# d232_board.net
KiCad netlist of a schematic drawn in EAGLE
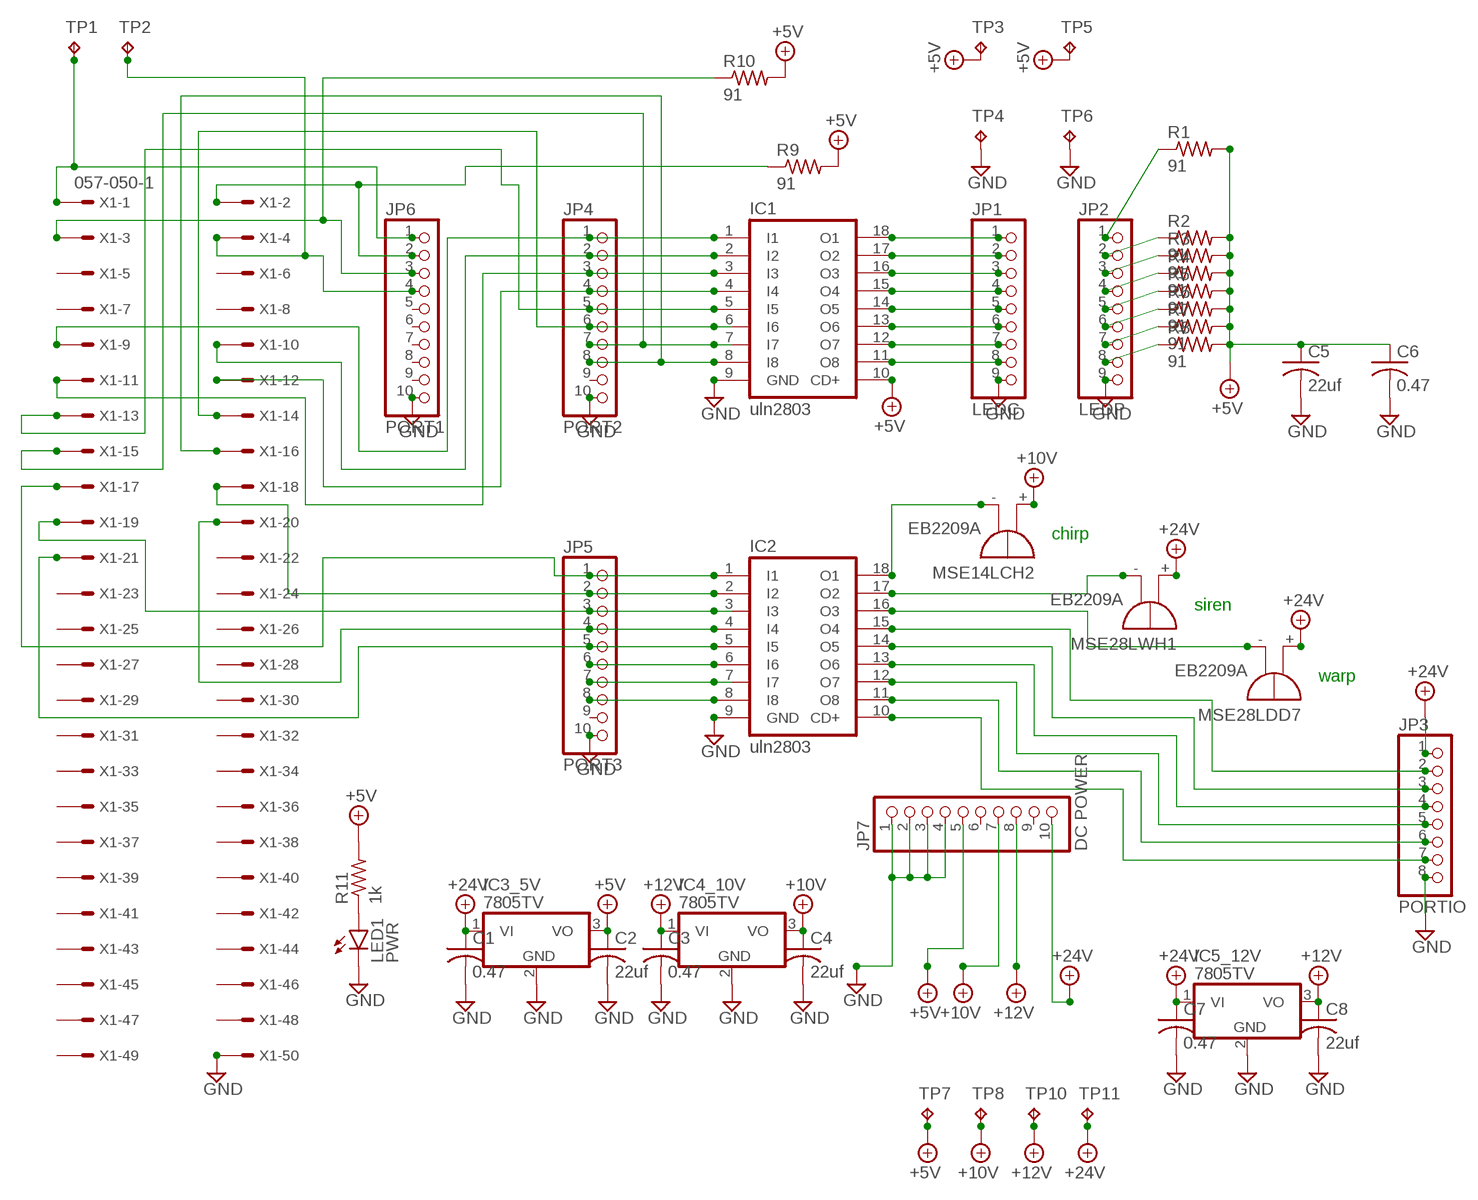
[diagram p0: schematic, sheet 1]

(export (version "E")
  (design (tool "Eeschema 10.0.6"))
  (components
    (comp (ref "C1")
      (value "0.47")
      (footprint "eagle-import:C1206K")
      (libsource (lib "eagle-import") (part "C-USC1206K"))
    )
    (comp (ref "C2")
      (value "22uf")
      (footprint "eagle-import:C1206K")
      (libsource (lib "eagle-import") (part "C-USC1206K"))
    )
    (comp (ref "C3")
      (value "0.47")
      (footprint "eagle-import:C1206K")
      (libsource (lib "eagle-import") (part "C-USC1206K"))
    )
    (comp (ref "C4")
      (value "22uf")
      (footprint "eagle-import:C1206K")
      (libsource (lib "eagle-import") (part "C-USC1206K"))
    )
    (comp (ref "C5")
      (value "22uf")
      (footprint "eagle-import:C1206K")
      (libsource (lib "eagle-import") (part "C-USC1206K"))
    )
    (comp (ref "C6")
      (value "0.47")
      (footprint "eagle-import:C1206K")
      (libsource (lib "eagle-import") (part "C-USC1206K"))
    )
    (comp (ref "C7")
      (value "0.47")
      (footprint "eagle-import:C1206K")
      (libsource (lib "eagle-import") (part "C-USC1206K"))
    )
    (comp (ref "C8")
      (value "22uf")
      (footprint "eagle-import:C1206K")
      (libsource (lib "eagle-import") (part "C-USC1206K"))
    )
    (comp (ref "IC1")
      (value "uln2803")
      (footprint "eagle-import:DIL18")
      (libsource (lib "eagle-import") (part "ULN2803A"))
    )
    (comp (ref "IC2")
      (value "uln2803")
      (footprint "eagle-import:DIL18")
      (libsource (lib "eagle-import") (part "ULN2803A"))
    )
    (comp (ref "IC3_5V")
      (value "7805TV")
      (footprint "eagle-import:TO220V")
      (libsource (lib "eagle-import") (part "78TV05"))
    )
    (comp (ref "IC4_10V")
      (value "7805TV")
      (footprint "eagle-import:TO220V")
      (libsource (lib "eagle-import") (part "78TV05"))
    )
    (comp (ref "IC5_12V")
      (value "7805TV")
      (footprint "eagle-import:TO220V")
      (libsource (lib "eagle-import") (part "78TV05"))
    )
    (comp (ref "JP1")
      (value "LEDC")
      (footprint "eagle-import:1X09")
      (libsource (lib "eagle-import") (part "PINHD-1X9"))
    )
    (comp (ref "JP2")
      (value "LEDP")
      (footprint "eagle-import:1X09")
      (libsource (lib "eagle-import") (part "PINHD-1X9"))
    )
    (comp (ref "JP3")
      (value "PORTIO")
      (footprint "eagle-import:1X08")
      (libsource (lib "eagle-import") (part "PINHD-1X8"))
    )
    (comp (ref "JP4")
      (value "PORT2")
      (footprint "eagle-import:1X10")
      (libsource (lib "eagle-import") (part "PINHD-1X10"))
    )
    (comp (ref "JP5")
      (value "PORT3")
      (footprint "eagle-import:1X10")
      (libsource (lib "eagle-import") (part "PINHD-1X10"))
    )
    (comp (ref "JP6")
      (value "PORT1")
      (footprint "eagle-import:1X10")
      (libsource (lib "eagle-import") (part "PINHD-1X10"))
    )
    (comp (ref "JP7")
      (value "DC POWER")
      (footprint "eagle-import:1X10")
      (libsource (lib "eagle-import") (part "PINHD-1X10"))
    )
    (comp (ref "LED1")
      (value "PWR")
      (footprint "eagle-import:CHIPLED_1206")
      (libsource (lib "eagle-import") (part "LEDCHIPLED_1206"))
    )
    (comp (ref "MSE14LCH2")
      (value "EB2209A")
      (footprint "eagle-import:EB2209A")
      (libsource (lib "eagle-import") (part "EB2209A"))
    )
    (comp (ref "MSE28LDD7")
      (value "EB2209A")
      (footprint "eagle-import:EB2209A")
      (libsource (lib "eagle-import") (part "EB2209A"))
    )
    (comp (ref "MSE28LWH1")
      (value "EB2209A")
      (footprint "eagle-import:EB2209A")
      (libsource (lib "eagle-import") (part "EB2209A"))
    )
    (comp (ref "R1")
      (value "91")
      (footprint "eagle-import:0204V")
      (libsource (lib "eagle-import") (part "R-US_0204/2V"))
    )
    (comp (ref "R2")
      (value "91")
      (footprint "eagle-import:0204V")
      (libsource (lib "eagle-import") (part "R-US_0204/2V"))
    )
    (comp (ref "R3")
      (value "91")
      (footprint "eagle-import:0204V")
      (libsource (lib "eagle-import") (part "R-US_0204/2V"))
    )
    (comp (ref "R4")
      (value "91")
      (footprint "eagle-import:0204V")
      (libsource (lib "eagle-import") (part "R-US_0204/2V"))
    )
    (comp (ref "R5")
      (value "91")
      (footprint "eagle-import:0204V")
      (libsource (lib "eagle-import") (part "R-US_0204/2V"))
    )
    (comp (ref "R6")
      (value "91")
      (footprint "eagle-import:0204V")
      (libsource (lib "eagle-import") (part "R-US_0204/2V"))
    )
    (comp (ref "R7")
      (value "91")
      (footprint "eagle-import:0204V")
      (libsource (lib "eagle-import") (part "R-US_0204/2V"))
    )
    (comp (ref "R8")
      (value "91")
      (footprint "eagle-import:0204V")
      (libsource (lib "eagle-import") (part "R-US_0204/2V"))
    )
    (comp (ref "R9")
      (value "91")
      (footprint "eagle-import:0204V")
      (libsource (lib "eagle-import") (part "R-US_0204/2V"))
    )
    (comp (ref "R10")
      (value "91")
      (footprint "eagle-import:0204V")
      (libsource (lib "eagle-import") (part "R-US_0204/2V"))
    )
    (comp (ref "R11")
      (value "1k")
      (footprint "eagle-import:0204V")
      (libsource (lib "eagle-import") (part "R-US_0204/2V"))
    )
    (comp (ref "TP1")
      (value "TPB2,54")
      (footprint "eagle-import:B2,54")
      (libsource (lib "eagle-import") (part "TPB2,54"))
    )
    (comp (ref "TP2")
      (value "TPB2,54")
      (footprint "eagle-import:B2,54")
      (libsource (lib "eagle-import") (part "TPB2,54"))
    )
    (comp (ref "TP3")
      (value "TPB2,54")
      (footprint "eagle-import:B2,54")
      (libsource (lib "eagle-import") (part "TPB2,54"))
    )
    (comp (ref "TP4")
      (value "TPB2,54")
      (footprint "eagle-import:B2,54")
      (libsource (lib "eagle-import") (part "TPB2,54"))
    )
    (comp (ref "TP5")
      (value "TPB2,54")
      (footprint "eagle-import:B2,54")
      (libsource (lib "eagle-import") (part "TPB2,54"))
    )
    (comp (ref "TP6")
      (value "TPB2,54")
      (footprint "eagle-import:B2,54")
      (libsource (lib "eagle-import") (part "TPB2,54"))
    )
    (comp (ref "TP7")
      (value "TPB2,54")
      (footprint "eagle-import:B2,54")
      (libsource (lib "eagle-import") (part "TPB2,54"))
    )
    (comp (ref "TP8")
      (value "TPB2,54")
      (footprint "eagle-import:B2,54")
      (libsource (lib "eagle-import") (part "TPB2,54"))
    )
    (comp (ref "TP10")
      (value "TPB2,54")
      (footprint "eagle-import:B2,54")
      (libsource (lib "eagle-import") (part "TPB2,54"))
    )
    (comp (ref "TP11")
      (value "TPB2,54")
      (footprint "eagle-import:B2,54")
      (libsource (lib "eagle-import") (part "TPB2,54"))
    )
    (comp (ref "X1")
      (value "057-050-1")
      (footprint "eagle-import:057-050-1")
      (libsource (lib "eagle-import") (part "057-050-1"))
    )
  )
  (nets
    (net (code "1") (name "+5V") (class "Default")
      (node (ref "C2") (pin "1") (pinfunction "1_1") (pintype "passive"))
      (node (ref "C5") (pin "1") (pinfunction "1_1") (pintype "passive"))
      (node (ref "C6") (pin "1") (pinfunction "1_1") (pintype "passive"))
      (node (ref "IC1") (pin "10") (pinfunction "CD+_10") (pintype "passive"))
      (node (ref "IC3_5V") (pin "3") (pinfunction "VO_3") (pintype "passive"))
      (node (ref "JP7") (pin "5") (pinfunction "5_5") (pintype "passive"))
      (node (ref "R1") (pin "2") (pinfunction "2_2") (pintype "passive"))
      (node (ref "R10") (pin "2") (pinfunction "2_2") (pintype "passive"))
      (node (ref "R11") (pin "2") (pinfunction "2_2") (pintype "passive"))
      (node (ref "R2") (pin "2") (pinfunction "2_2") (pintype "passive"))
      (node (ref "R3") (pin "2") (pinfunction "2_2") (pintype "passive"))
      (node (ref "R4") (pin "2") (pinfunction "2_2") (pintype "passive"))
      (node (ref "R5") (pin "2") (pinfunction "2_2") (pintype "passive"))
      (node (ref "R6") (pin "2") (pinfunction "2_2") (pintype "passive"))
      (node (ref "R7") (pin "2") (pinfunction "2_2") (pintype "passive"))
      (node (ref "R8") (pin "2") (pinfunction "2_2") (pintype "passive"))
      (node (ref "R9") (pin "2") (pinfunction "2_2") (pintype "passive"))
      (node (ref "TP3") (pin "TP") (pinfunction "TP_TP") (pintype "input"))
      (node (ref "TP5") (pin "TP") (pinfunction "TP_TP") (pintype "input"))
      (node (ref "TP7") (pin "TP") (pinfunction "TP_TP") (pintype "input"))
    )
    (net (code "2") (name "+10V") (class "Default")
      (node (ref "C4") (pin "1") (pinfunction "1_1") (pintype "passive"))
      (node (ref "IC4_10V") (pin "3") (pinfunction "VO_3") (pintype "passive"))
      (node (ref "JP7") (pin "7") (pinfunction "7_7") (pintype "passive"))
      (node (ref "MSE14LCH2") (pin "+") (pinfunction "+_+") (pintype "passive"))
      (node (ref "TP8") (pin "TP") (pinfunction "TP_TP") (pintype "input"))
    )
    (net (code "3") (name "+12V") (class "Default")
      (node (ref "C3") (pin "1") (pinfunction "1_1") (pintype "passive"))
      (node (ref "C8") (pin "1") (pinfunction "1_1") (pintype "passive"))
      (node (ref "IC4_10V") (pin "1") (pinfunction "VI_1") (pintype "input"))
      (node (ref "IC5_12V") (pin "3") (pinfunction "VO_3") (pintype "passive"))
      (node (ref "JP7") (pin "8") (pinfunction "8_8") (pintype "passive"))
      (node (ref "TP10") (pin "TP") (pinfunction "TP_TP") (pintype "input"))
    )
    (net (code "4") (name "+24V") (class "Default")
      (node (ref "C1") (pin "1") (pinfunction "1_1") (pintype "passive"))
      (node (ref "C7") (pin "1") (pinfunction "1_1") (pintype "passive"))
      (node (ref "IC3_5V") (pin "1") (pinfunction "VI_1") (pintype "input"))
      (node (ref "IC5_12V") (pin "1") (pinfunction "VI_1") (pintype "input"))
      (node (ref "JP3") (pin "1") (pinfunction "1_1") (pintype "passive"))
      (node (ref "JP7") (pin "10") (pinfunction "10_10") (pintype "passive"))
      (node (ref "MSE28LDD7") (pin "+") (pinfunction "+_+") (pintype "passive"))
      (node (ref "MSE28LWH1") (pin "+") (pinfunction "+_+") (pintype "passive"))
      (node (ref "TP11") (pin "TP") (pinfunction "TP_TP") (pintype "input"))
    )
    (net (code "5") (name "GND") (class "Default")
      (node (ref "C1") (pin "2") (pinfunction "2_2") (pintype "passive"))
      (node (ref "C2") (pin "2") (pinfunction "2_2") (pintype "passive"))
      (node (ref "C3") (pin "2") (pinfunction "2_2") (pintype "passive"))
      (node (ref "C4") (pin "2") (pinfunction "2_2") (pintype "passive"))
      (node (ref "C5") (pin "2") (pinfunction "2_2") (pintype "passive"))
      (node (ref "C6") (pin "2") (pinfunction "2_2") (pintype "passive"))
      (node (ref "C7") (pin "2") (pinfunction "2_2") (pintype "passive"))
      (node (ref "C8") (pin "2") (pinfunction "2_2") (pintype "passive"))
      (node (ref "IC1") (pin "9") (pinfunction "GND_9") (pintype "power_in"))
      (node (ref "IC2") (pin "9") (pinfunction "GND_9") (pintype "power_in"))
      (node (ref "IC3_5V") (pin "2") (pinfunction "GND_2") (pintype "passive"))
      (node (ref "IC4_10V") (pin "2") (pinfunction "GND_2") (pintype "passive"))
      (node (ref "IC5_12V") (pin "2") (pinfunction "GND_2") (pintype "passive"))
      (node (ref "JP1") (pin "9") (pinfunction "9_9") (pintype "passive"))
      (node (ref "JP2") (pin "9") (pinfunction "9_9") (pintype "passive"))
      (node (ref "JP3") (pin "8") (pinfunction "8_8") (pintype "passive"))
      (node (ref "JP4") (pin "10") (pinfunction "10_10") (pintype "passive"))
      (node (ref "JP5") (pin "10") (pinfunction "10_10") (pintype "passive"))
      (node (ref "JP6") (pin "10") (pinfunction "10_10") (pintype "passive"))
      (node (ref "JP7") (pin "1") (pinfunction "1_1") (pintype "passive"))
      (node (ref "JP7") (pin "2") (pinfunction "2_2") (pintype "passive"))
      (node (ref "JP7") (pin "3") (pinfunction "3_3") (pintype "passive"))
      (node (ref "JP7") (pin "4") (pinfunction "4_4") (pintype "passive"))
      (node (ref "LED1") (pin "C") (pinfunction "C_C") (pintype "passive"))
      (node (ref "TP4") (pin "TP") (pinfunction "TP_TP") (pintype "input"))
      (node (ref "TP6") (pin "TP") (pinfunction "TP_TP") (pintype "input"))
      (node (ref "X1") (pin "50") (pinfunction "S_50") (pintype "passive"))
    )
    (net (code "6") (name "Net-(IC1-I1)") (class "Default")
      (node (ref "IC1") (pin "1") (pinfunction "I1_1") (pintype "input"))
      (node (ref "JP4") (pin "1") (pinfunction "1_1") (pintype "passive"))
      (node (ref "X1") (pin "9") (pinfunction "S_9") (pintype "passive"))
    )
    (net (code "7") (name "Net-(IC1-I2)") (class "Default")
      (node (ref "IC1") (pin "2") (pinfunction "I2_2") (pintype "input"))
      (node (ref "JP4") (pin "2") (pinfunction "2_2") (pintype "passive"))
      (node (ref "X1") (pin "10") (pinfunction "S_10") (pintype "passive"))
    )
    (net (code "8") (name "Net-(IC1-I3)") (class "Default")
      (node (ref "IC1") (pin "3") (pinfunction "I3_3") (pintype "input"))
      (node (ref "JP4") (pin "3") (pinfunction "3_3") (pintype "passive"))
      (node (ref "X1") (pin "11") (pinfunction "S_11") (pintype "passive"))
    )
    (net (code "9") (name "Net-(IC1-I4)") (class "Default")
      (node (ref "IC1") (pin "4") (pinfunction "I4_4") (pintype "input"))
      (node (ref "JP4") (pin "4") (pinfunction "4_4") (pintype "passive"))
      (node (ref "X1") (pin "12") (pinfunction "S_12") (pintype "passive"))
    )
    (net (code "10") (name "Net-(IC1-I5)") (class "Default")
      (node (ref "IC1") (pin "5") (pinfunction "I5_5") (pintype "input"))
      (node (ref "JP4") (pin "5") (pinfunction "5_5") (pintype "passive"))
      (node (ref "X1") (pin "13") (pinfunction "S_13") (pintype "passive"))
    )
    (net (code "11") (name "Net-(IC1-I6)") (class "Default")
      (node (ref "IC1") (pin "6") (pinfunction "I6_6") (pintype "input"))
      (node (ref "JP4") (pin "6") (pinfunction "6_6") (pintype "passive"))
      (node (ref "X1") (pin "14") (pinfunction "S_14") (pintype "passive"))
    )
    (net (code "12") (name "Net-(IC1-I7)") (class "Default")
      (node (ref "IC1") (pin "7") (pinfunction "I7_7") (pintype "input"))
      (node (ref "JP4") (pin "7") (pinfunction "7_7") (pintype "passive"))
      (node (ref "X1") (pin "15") (pinfunction "S_15") (pintype "passive"))
    )
    (net (code "13") (name "Net-(IC1-I8)") (class "Default")
      (node (ref "IC1") (pin "8") (pinfunction "I8_8") (pintype "input"))
      (node (ref "JP4") (pin "8") (pinfunction "8_8") (pintype "passive"))
      (node (ref "X1") (pin "16") (pinfunction "S_16") (pintype "passive"))
    )
    (net (code "14") (name "Net-(IC1-O1)") (class "Default")
      (node (ref "IC1") (pin "18") (pinfunction "O1_18") (pintype "open_collector"))
      (node (ref "JP1") (pin "1") (pinfunction "1_1") (pintype "passive"))
    )
    (net (code "15") (name "Net-(IC1-O2)") (class "Default")
      (node (ref "IC1") (pin "17") (pinfunction "O2_17") (pintype "open_collector"))
      (node (ref "JP1") (pin "2") (pinfunction "2_2") (pintype "passive"))
    )
    (net (code "16") (name "Net-(IC1-O3)") (class "Default")
      (node (ref "IC1") (pin "16") (pinfunction "O3_16") (pintype "open_collector"))
      (node (ref "JP1") (pin "3") (pinfunction "3_3") (pintype "passive"))
    )
    (net (code "17") (name "Net-(IC1-O4)") (class "Default")
      (node (ref "IC1") (pin "15") (pinfunction "O4_15") (pintype "open_collector"))
      (node (ref "JP1") (pin "4") (pinfunction "4_4") (pintype "passive"))
    )
    (net (code "18") (name "Net-(IC1-O5)") (class "Default")
      (node (ref "IC1") (pin "14") (pinfunction "O5_14") (pintype "open_collector"))
      (node (ref "JP1") (pin "5") (pinfunction "5_5") (pintype "passive"))
    )
    (net (code "19") (name "Net-(IC1-O6)") (class "Default")
      (node (ref "IC1") (pin "13") (pinfunction "O6_13") (pintype "open_collector"))
      (node (ref "JP1") (pin "6") (pinfunction "6_6") (pintype "passive"))
    )
    (net (code "20") (name "Net-(IC1-O7)") (class "Default")
      (node (ref "IC1") (pin "12") (pinfunction "O7_12") (pintype "open_collector"))
      (node (ref "JP1") (pin "7") (pinfunction "7_7") (pintype "passive"))
    )
    (net (code "21") (name "Net-(IC1-O8)") (class "Default")
      (node (ref "IC1") (pin "11") (pinfunction "O8_11") (pintype "open_collector"))
      (node (ref "JP1") (pin "8") (pinfunction "8_8") (pintype "passive"))
    )
    (net (code "22") (name "Net-(IC2-CD+)") (class "Default")
      (node (ref "IC2") (pin "10") (pinfunction "CD+_10") (pintype "passive"))
      (node (ref "JP3") (pin "7") (pinfunction "7_7") (pintype "passive"))
    )
    (net (code "23") (name "Net-(IC2-I1)") (class "Default")
      (node (ref "IC2") (pin "1") (pinfunction "I1_1") (pintype "input"))
      (node (ref "JP5") (pin "1") (pinfunction "1_1") (pintype "passive"))
      (node (ref "X1") (pin "17") (pinfunction "S_17") (pintype "passive"))
    )
    (net (code "24") (name "Net-(IC2-I2)") (class "Default")
      (node (ref "IC2") (pin "2") (pinfunction "I2_2") (pintype "input"))
      (node (ref "JP5") (pin "2") (pinfunction "2_2") (pintype "passive"))
      (node (ref "X1") (pin "18") (pinfunction "S_18") (pintype "passive"))
    )
    (net (code "25") (name "Net-(IC2-I3)") (class "Default")
      (node (ref "IC2") (pin "3") (pinfunction "I3_3") (pintype "input"))
      (node (ref "JP5") (pin "3") (pinfunction "3_3") (pintype "passive"))
      (node (ref "X1") (pin "19") (pinfunction "S_19") (pintype "passive"))
    )
    (net (code "26") (name "Net-(IC2-I4)") (class "Default")
      (node (ref "IC2") (pin "4") (pinfunction "I4_4") (pintype "input"))
      (node (ref "JP5") (pin "4") (pinfunction "4_4") (pintype "passive"))
      (node (ref "X1") (pin "20") (pinfunction "S_20") (pintype "passive"))
    )
    (net (code "27") (name "Net-(IC2-I5)") (class "Default")
      (node (ref "IC2") (pin "5") (pinfunction "I5_5") (pintype "input"))
      (node (ref "JP5") (pin "5") (pinfunction "5_5") (pintype "passive"))
      (node (ref "X1") (pin "21") (pinfunction "S_21") (pintype "passive"))
    )
    (net (code "28") (name "Net-(IC2-I6)") (class "Default")
      (node (ref "IC2") (pin "6") (pinfunction "I6_6") (pintype "input"))
      (node (ref "JP5") (pin "6") (pinfunction "6_6") (pintype "passive"))
    )
    (net (code "29") (name "Net-(IC2-I7)") (class "Default")
      (node (ref "IC2") (pin "7") (pinfunction "I7_7") (pintype "input"))
      (node (ref "JP5") (pin "7") (pinfunction "7_7") (pintype "passive"))
    )
    (net (code "30") (name "Net-(IC2-I8)") (class "Default")
      (node (ref "IC2") (pin "8") (pinfunction "I8_8") (pintype "input"))
      (node (ref "JP5") (pin "8") (pinfunction "8_8") (pintype "passive"))
    )
    (net (code "31") (name "Net-(IC2-O1)") (class "Default")
      (node (ref "IC2") (pin "18") (pinfunction "O1_18") (pintype "open_collector"))
      (node (ref "MSE14LCH2") (pin "-") (pinfunction "-_-") (pintype "passive"))
    )
    (net (code "32") (name "Net-(IC2-O2)") (class "Default")
      (node (ref "IC2") (pin "17") (pinfunction "O2_17") (pintype "open_collector"))
      (node (ref "MSE28LWH1") (pin "-") (pinfunction "-_-") (pintype "passive"))
    )
    (net (code "33") (name "Net-(IC2-O3)") (class "Default")
      (node (ref "IC2") (pin "16") (pinfunction "O3_16") (pintype "open_collector"))
      (node (ref "MSE28LDD7") (pin "-") (pinfunction "-_-") (pintype "passive"))
    )
    (net (code "34") (name "Net-(IC2-O4)") (class "Default")
      (node (ref "IC2") (pin "15") (pinfunction "O4_15") (pintype "open_collector"))
      (node (ref "JP3") (pin "2") (pinfunction "2_2") (pintype "passive"))
    )
    (net (code "35") (name "Net-(IC2-O5)") (class "Default")
      (node (ref "IC2") (pin "14") (pinfunction "O5_14") (pintype "open_collector"))
      (node (ref "JP3") (pin "3") (pinfunction "3_3") (pintype "passive"))
    )
    (net (code "36") (name "Net-(IC2-O6)") (class "Default")
      (node (ref "IC2") (pin "13") (pinfunction "O6_13") (pintype "open_collector"))
      (node (ref "JP3") (pin "4") (pinfunction "4_4") (pintype "passive"))
    )
    (net (code "37") (name "Net-(IC2-O7)") (class "Default")
      (node (ref "IC2") (pin "12") (pinfunction "O7_12") (pintype "open_collector"))
      (node (ref "JP3") (pin "5") (pinfunction "5_5") (pintype "passive"))
    )
    (net (code "38") (name "Net-(IC2-O8)") (class "Default")
      (node (ref "IC2") (pin "11") (pinfunction "O8_11") (pintype "open_collector"))
      (node (ref "JP3") (pin "6") (pinfunction "6_6") (pintype "passive"))
    )
    (net (code "39") (name "Net-(JP2-Pad1)") (class "Default")
      (node (ref "JP2") (pin "1") (pinfunction "1_1") (pintype "passive"))
      (node (ref "R1") (pin "1") (pinfunction "1_1") (pintype "passive"))
    )
    (net (code "40") (name "Net-(JP2-Pad2)") (class "Default")
      (node (ref "JP2") (pin "2") (pinfunction "2_2") (pintype "passive"))
      (node (ref "R2") (pin "1") (pinfunction "1_1") (pintype "passive"))
    )
    (net (code "41") (name "Net-(JP2-Pad3)") (class "Default")
      (node (ref "JP2") (pin "3") (pinfunction "3_3") (pintype "passive"))
      (node (ref "R3") (pin "1") (pinfunction "1_1") (pintype "passive"))
    )
    (net (code "42") (name "Net-(JP2-Pad4)") (class "Default")
      (node (ref "JP2") (pin "4") (pinfunction "4_4") (pintype "passive"))
      (node (ref "R4") (pin "1") (pinfunction "1_1") (pintype "passive"))
    )
    (net (code "43") (name "Net-(JP2-Pad5)") (class "Default")
      (node (ref "JP2") (pin "5") (pinfunction "5_5") (pintype "passive"))
      (node (ref "R5") (pin "1") (pinfunction "1_1") (pintype "passive"))
    )
    (net (code "44") (name "Net-(JP2-Pad6)") (class "Default")
      (node (ref "JP2") (pin "6") (pinfunction "6_6") (pintype "passive"))
      (node (ref "R6") (pin "1") (pinfunction "1_1") (pintype "passive"))
    )
    (net (code "45") (name "Net-(JP2-Pad7)") (class "Default")
      (node (ref "JP2") (pin "7") (pinfunction "7_7") (pintype "passive"))
      (node (ref "R7") (pin "1") (pinfunction "1_1") (pintype "passive"))
    )
    (net (code "46") (name "Net-(JP2-Pad8)") (class "Default")
      (node (ref "JP2") (pin "8") (pinfunction "8_8") (pintype "passive"))
      (node (ref "R8") (pin "1") (pinfunction "1_1") (pintype "passive"))
    )
    (net (code "47") (name "Net-(LED1-PadA)") (class "Default")
      (node (ref "LED1") (pin "A") (pinfunction "A_A") (pintype "passive"))
      (node (ref "R11") (pin "1") (pinfunction "1_1") (pintype "passive"))
    )
    (net (code "48") (name "Net-(X1A-S)") (class "Default")
      (node (ref "JP6") (pin "1") (pinfunction "1_1") (pintype "passive"))
      (node (ref "TP1") (pin "TP") (pinfunction "TP_TP") (pintype "input"))
      (node (ref "X1") (pin "1") (pinfunction "S_1") (pintype "passive"))
    )
    (net (code "49") (name "Net-(X1AH-S)") (class "Default")
      (node (ref "JP6") (pin "4") (pinfunction "4_4") (pintype "passive"))
      (node (ref "TP2") (pin "TP") (pinfunction "TP_TP") (pintype "input"))
      (node (ref "X1") (pin "4") (pinfunction "S_4") (pintype "passive"))
    )
    (net (code "50") (name "Net-(X1L-S)") (class "Default")
      (node (ref "JP6") (pin "2") (pinfunction "2_2") (pintype "passive"))
      (node (ref "R9") (pin "1") (pinfunction "1_1") (pintype "passive"))
      (node (ref "X1") (pin "2") (pinfunction "S_2") (pintype "passive"))
    )
    (net (code "51") (name "Net-(X1W-S)") (class "Default")
      (node (ref "JP6") (pin "3") (pinfunction "3_3") (pintype "passive"))
      (node (ref "R10") (pin "1") (pinfunction "1_1") (pintype "passive"))
      (node (ref "X1") (pin "3") (pinfunction "S_3") (pintype "passive"))
    )
    (net (code "52") (name "unconnected-(JP4-Pad9)") (class "Default")
      (node (ref "JP4") (pin "9") (pinfunction "9_9") (pintype "passive"))
    )
    (net (code "53") (name "unconnected-(JP5-Pad9)") (class "Default")
      (node (ref "JP5") (pin "9") (pinfunction "9_9") (pintype "passive"))
    )
    (net (code "54") (name "unconnected-(JP6-Pad5)") (class "Default")
      (node (ref "JP6") (pin "5") (pinfunction "5_5") (pintype "passive"))
    )
    (net (code "55") (name "unconnected-(JP6-Pad6)") (class "Default")
      (node (ref "JP6") (pin "6") (pinfunction "6_6") (pintype "passive"))
    )
    (net (code "56") (name "unconnected-(JP6-Pad7)") (class "Default")
      (node (ref "JP6") (pin "7") (pinfunction "7_7") (pintype "passive"))
    )
    (net (code "57") (name "unconnected-(JP6-Pad8)") (class "Default")
      (node (ref "JP6") (pin "8") (pinfunction "8_8") (pintype "passive"))
    )
    (net (code "58") (name "unconnected-(JP6-Pad9)") (class "Default")
      (node (ref "JP6") (pin "9") (pinfunction "9_9") (pintype "passive"))
    )
    (net (code "59") (name "unconnected-(JP7-Pad6)") (class "Default")
      (node (ref "JP7") (pin "6") (pinfunction "6_6") (pintype "passive"))
    )
    (net (code "60") (name "unconnected-(JP7-Pad9)") (class "Default")
      (node (ref "JP7") (pin "9") (pinfunction "9_9") (pintype "passive"))
    )
    (net (code "61") (name "unconnected-(X1AA-S-Pad33)") (class "Default")
      (node (ref "X1") (pin "33") (pinfunction "S_33") (pintype "passive"))
    )
    (net (code "62") (name "unconnected-(X1AB-S-Pad34)") (class "Default")
      (node (ref "X1") (pin "34") (pinfunction "S_34") (pintype "passive"))
    )
    (net (code "63") (name "unconnected-(X1AC-S-Pad35)") (class "Default")
      (node (ref "X1") (pin "35") (pinfunction "S_35") (pintype "passive"))
    )
    (net (code "64") (name "unconnected-(X1AD-S-Pad36)") (class "Default")
      (node (ref "X1") (pin "36") (pinfunction "S_36") (pintype "passive"))
    )
    (net (code "65") (name "unconnected-(X1AE-S-Pad37)") (class "Default")
      (node (ref "X1") (pin "37") (pinfunction "S_37") (pintype "passive"))
    )
    (net (code "66") (name "unconnected-(X1AF-S-Pad38)") (class "Default")
      (node (ref "X1") (pin "38") (pinfunction "S_38") (pintype "passive"))
    )
    (net (code "67") (name "unconnected-(X1AG-S-Pad39)") (class "Default")
      (node (ref "X1") (pin "39") (pinfunction "S_39") (pintype "passive"))
    )
    (net (code "68") (name "unconnected-(X1AI-S-Pad40)") (class "Default")
      (node (ref "X1") (pin "40") (pinfunction "S_40") (pintype "passive"))
    )
    (net (code "69") (name "unconnected-(X1AJ-S-Pad41)") (class "Default")
      (node (ref "X1") (pin "41") (pinfunction "S_41") (pintype "passive"))
    )
    (net (code "70") (name "unconnected-(X1AK-S-Pad42)") (class "Default")
      (node (ref "X1") (pin "42") (pinfunction "S_42") (pintype "passive"))
    )
    (net (code "71") (name "unconnected-(X1AL-S-Pad43)") (class "Default")
      (node (ref "X1") (pin "43") (pinfunction "S_43") (pintype "passive"))
    )
    (net (code "72") (name "unconnected-(X1AM-S-Pad44)") (class "Default")
      (node (ref "X1") (pin "44") (pinfunction "S_44") (pintype "passive"))
    )
    (net (code "73") (name "unconnected-(X1AN-S-Pad45)") (class "Default")
      (node (ref "X1") (pin "45") (pinfunction "S_45") (pintype "passive"))
    )
    (net (code "74") (name "unconnected-(X1AO-S-Pad46)") (class "Default")
      (node (ref "X1") (pin "46") (pinfunction "S_46") (pintype "passive"))
    )
    (net (code "75") (name "unconnected-(X1AP-S-Pad47)") (class "Default")
      (node (ref "X1") (pin "47") (pinfunction "S_47") (pintype "passive"))
    )
    (net (code "76") (name "unconnected-(X1AQ-S-Pad48)") (class "Default")
      (node (ref "X1") (pin "48") (pinfunction "S_48") (pintype "passive"))
    )
    (net (code "77") (name "unconnected-(X1AR-S-Pad49)") (class "Default")
      (node (ref "X1") (pin "49") (pinfunction "S_49") (pintype "passive"))
    )
    (net (code "78") (name "unconnected-(X1AS-S-Pad5)") (class "Default")
      (node (ref "X1") (pin "5") (pinfunction "S_5") (pintype "passive"))
    )
    (net (code "79") (name "unconnected-(X1AU-S-Pad6)") (class "Default")
      (node (ref "X1") (pin "6") (pinfunction "S_6") (pintype "passive"))
    )
    (net (code "80") (name "unconnected-(X1AV-S-Pad7)") (class "Default")
      (node (ref "X1") (pin "7") (pinfunction "S_7") (pintype "passive"))
    )
    (net (code "81") (name "unconnected-(X1AW-S-Pad8)") (class "Default")
      (node (ref "X1") (pin "8") (pinfunction "S_8") (pintype "passive"))
    )
    (net (code "82") (name "unconnected-(X1O-S-Pad22)") (class "Default")
      (node (ref "X1") (pin "22") (pinfunction "S_22") (pintype "passive"))
    )
    (net (code "83") (name "unconnected-(X1P-S-Pad23)") (class "Default")
      (node (ref "X1") (pin "23") (pinfunction "S_23") (pintype "passive"))
    )
    (net (code "84") (name "unconnected-(X1Q-S-Pad24)") (class "Default")
      (node (ref "X1") (pin "24") (pinfunction "S_24") (pintype "passive"))
    )
    (net (code "85") (name "unconnected-(X1R-S-Pad25)") (class "Default")
      (node (ref "X1") (pin "25") (pinfunction "S_25") (pintype "passive"))
    )
    (net (code "86") (name "unconnected-(X1S-S-Pad26)") (class "Default")
      (node (ref "X1") (pin "26") (pinfunction "S_26") (pintype "passive"))
    )
    (net (code "87") (name "unconnected-(X1T-S-Pad27)") (class "Default")
      (node (ref "X1") (pin "27") (pinfunction "S_27") (pintype "passive"))
    )
    (net (code "88") (name "unconnected-(X1U-S-Pad28)") (class "Default")
      (node (ref "X1") (pin "28") (pinfunction "S_28") (pintype "passive"))
    )
    (net (code "89") (name "unconnected-(X1V-S-Pad29)") (class "Default")
      (node (ref "X1") (pin "29") (pinfunction "S_29") (pintype "passive"))
    )
    (net (code "90") (name "unconnected-(X1X-S-Pad30)") (class "Default")
      (node (ref "X1") (pin "30") (pinfunction "S_30") (pintype "passive"))
    )
    (net (code "91") (name "unconnected-(X1Y-S-Pad31)") (class "Default")
      (node (ref "X1") (pin "31") (pinfunction "S_31") (pintype "passive"))
    )
    (net (code "92") (name "unconnected-(X1Z-S-Pad32)") (class "Default")
      (node (ref "X1") (pin "32") (pinfunction "S_32") (pintype "passive"))
    )
  )
)
